# AC_Outlet_Top.net
KiCad netlist of a schematic drawn in Altium Designer
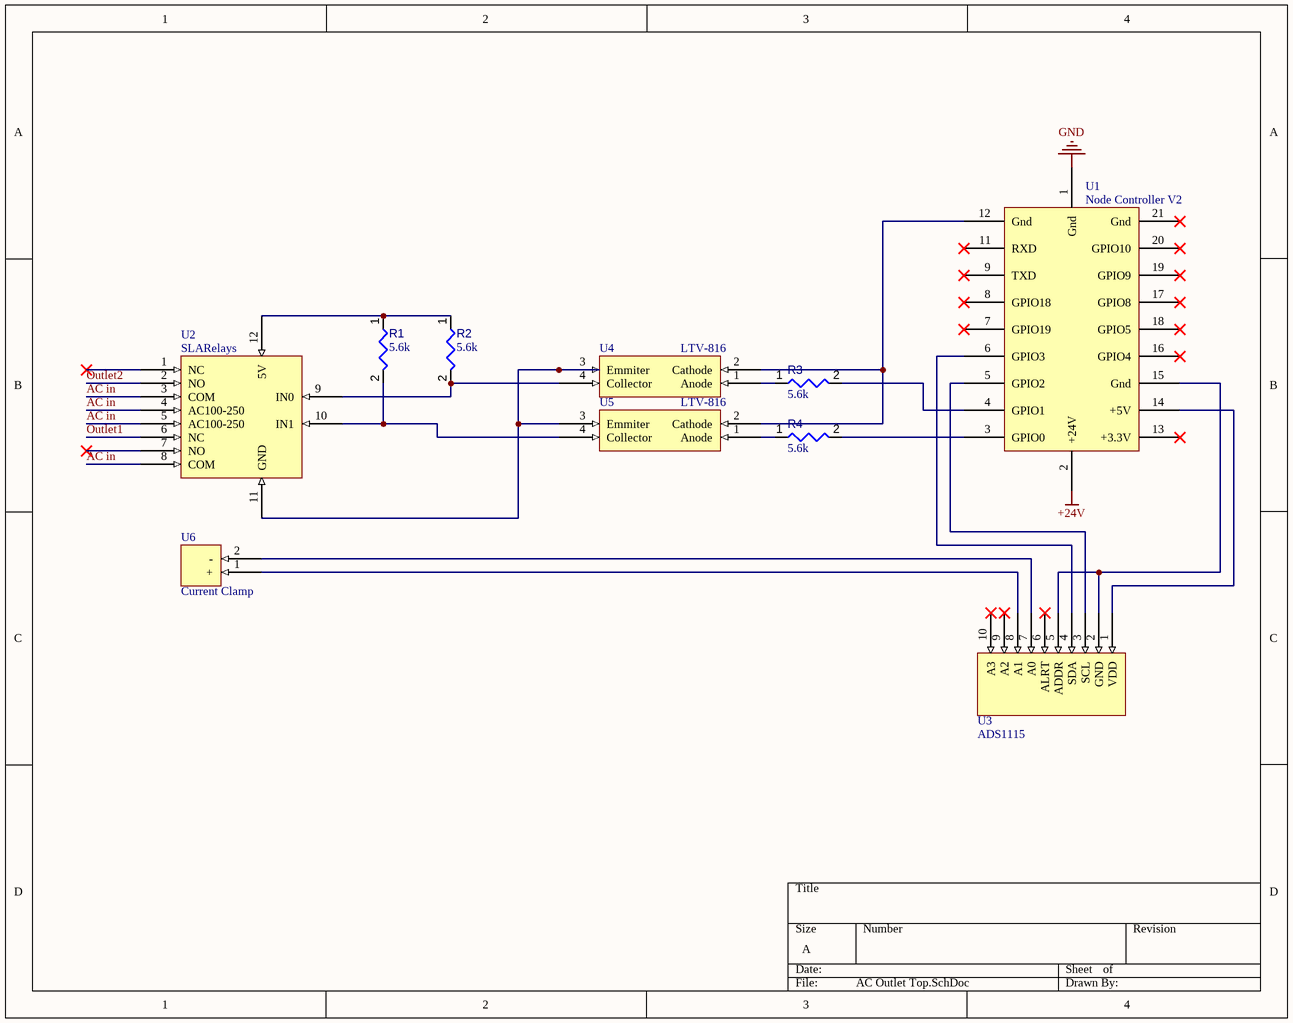
[diagram p0: AC Outlet Top.SchDoc]

(export (version "E")
  (design (tool "Eeschema 10.0.6"))
  (components
    (comp (ref "R1")
      (value "5.6k")
      (footprint "RESC0402(1005)_L")
      (description "Chip Resistor, 5,6 kOhms, +/-5 %, 63 mW, -55 to 155 degC, 0402")
      (fields (field (name "POWER") "63mW") (field (name "TOLERANCE") "5%"))
      (libsource (lib "C0514760 C0514760") (part "RES-2"))
    )
    (comp (ref "R2")
      (value "5.6k")
      (footprint "RESC0402(1005)_L")
      (description "Chip Resistor, 5,6 kOhms, +/-5 %, 63 mW, -55 to 155 degC, 0402")
      (fields (field (name "POWER") "63mW") (field (name "TOLERANCE") "5%"))
      (libsource (lib "C0514760 C0514760") (part "RES-2"))
    )
    (comp (ref "R3")
      (value "5.6k")
      (footprint "RESC0402(1005)_L")
      (description "Chip Resistor, 5,6 kOhms, +/-5 %, 63 mW, -55 to 155 degC, 0402")
      (fields (field (name "POWER") "63mW") (field (name "TOLERANCE") "5%"))
      (libsource (lib "C0514760 C0514760") (part "RES-2"))
    )
    (comp (ref "R4")
      (value "5.6k")
      (footprint "RESC0402(1005)_L")
      (description "Chip Resistor, 5,6 kOhms, +/-5 %, 63 mW, -55 to 155 degC, 0402")
      (fields (field (name "POWER") "63mW") (field (name "TOLERANCE") "5%"))
      (libsource (lib "C0514760 C0514760") (part "RES-2"))
    )
    (comp (ref "U1") (value "Node Controller V2") (libsource (lib "AC Outlet") (part "Node Controller V2")))
    (comp (ref "U2") (value "SLARelays") (libsource (lib "AC Outlet") (part "SLARelays")))
    (comp (ref "U3") (value "ADS1115") (libsource (lib "AC Outlet") (part "ADS1115")))
    (comp (ref "U4") (value "LTV-816") (libsource (lib "AC Outlet") (part "LTV-816")))
    (comp (ref "U5") (value "LTV-816") (libsource (lib "AC Outlet") (part "LTV-816")))
    (comp (ref "U6") (value "Current Clamp") (libsource (lib "AC Outlet") (part "Current Clamp")))
  )
  (nets
    (net (code "1") (name "+24V") (class "Default")
      (node (ref "U1") (pin "2") (pinfunction "+24V_2") (pintype "passive"))
    )
    (net (code "2") (name "/AC in") (class "Default")
      (node (ref "U2") (pin "3") (pinfunction "COM_3") (pintype "input"))
      (node (ref "U2") (pin "4") (pinfunction "AC100-250_4") (pintype "input"))
      (node (ref "U2") (pin "5") (pinfunction "AC100-250_5") (pintype "input"))
      (node (ref "U2") (pin "8") (pinfunction "COM_8") (pintype "input"))
    )
    (net (code "3") (name "/Outlet1") (class "Default")
      (node (ref "U2") (pin "6") (pinfunction "NC_6") (pintype "input"))
    )
    (net (code "4") (name "/Outlet2") (class "Default")
      (node (ref "U2") (pin "2") (pinfunction "NO_2") (pintype "input"))
    )
    (net (code "5") (name "GND") (class "Default")
      (node (ref "U1") (pin "1") (pinfunction "Gnd_1") (pintype "passive"))
    )
    (net (code "6") (name "Net-(U1-+5V)") (class "Default")
      (node (ref "U1") (pin "14") (pinfunction "+5V_14") (pintype "passive"))
      (node (ref "U3") (pin "1") (pinfunction "VDD_1") (pintype "input"))
    )
    (net (code "7") (name "Net-(U1-GPIO0)") (class "Default")
      (node (ref "R4") (pin "2") (pinfunction "2_2") (pintype "passive"))
      (node (ref "U1") (pin "3") (pinfunction "GPIO0_3") (pintype "passive"))
    )
    (net (code "8") (name "Net-(U1-GPIO1)") (class "Default")
      (node (ref "R3") (pin "2") (pinfunction "2_2") (pintype "passive"))
      (node (ref "U1") (pin "4") (pinfunction "GPIO1_4") (pintype "passive"))
    )
    (net (code "9") (name "Net-(U1-GPIO2)") (class "Default")
      (node (ref "U1") (pin "5") (pinfunction "GPIO2_5") (pintype "passive"))
      (node (ref "U3") (pin "3") (pinfunction "SCL_3") (pintype "input"))
    )
    (net (code "10") (name "Net-(U1-GPIO3)") (class "Default")
      (node (ref "U1") (pin "6") (pinfunction "GPIO3_6") (pintype "passive"))
      (node (ref "U3") (pin "4") (pinfunction "SDA_4") (pintype "input"))
    )
    (net (code "11") (name "Net-(U2-5V)") (class "Default")
      (node (ref "R1") (pin "1") (pinfunction "1_1") (pintype "passive"))
      (node (ref "R2") (pin "1") (pinfunction "1_1") (pintype "passive"))
      (node (ref "U2") (pin "12") (pinfunction "5V_12") (pintype "input"))
    )
    (net (code "12") (name "Net-(U2-GND)") (class "Default")
      (node (ref "U2") (pin "11") (pinfunction "GND_11") (pintype "input"))
      (node (ref "U4") (pin "3") (pinfunction "Emmiter_3") (pintype "input"))
      (node (ref "U5") (pin "3") (pinfunction "Emmiter_3") (pintype "input"))
    )
    (net (code "13") (name "Net-(U2-IN0)") (class "Default")
      (node (ref "R2") (pin "2") (pinfunction "2_2") (pintype "passive"))
      (node (ref "U2") (pin "9") (pinfunction "IN0_9") (pintype "input"))
      (node (ref "U4") (pin "4") (pinfunction "Collector_4") (pintype "input"))
    )
    (net (code "14") (name "Net-(U2-IN1)") (class "Default")
      (node (ref "R1") (pin "2") (pinfunction "2_2") (pintype "passive"))
      (node (ref "U2") (pin "10") (pinfunction "IN1_10") (pintype "input"))
      (node (ref "U5") (pin "4") (pinfunction "Collector_4") (pintype "input"))
    )
    (net (code "15") (name "Net-(U3-A0)") (class "Default")
      (node (ref "U3") (pin "7") (pinfunction "A0_7") (pintype "input"))
      (node (ref "U6") (pin "2") (pinfunction "-_2") (pintype "input"))
    )
    (net (code "16") (name "Net-(U3-A1)") (class "Default")
      (node (ref "U3") (pin "8") (pinfunction "A1_8") (pintype "input"))
      (node (ref "U6") (pin "1") (pinfunction "+_1") (pintype "input"))
    )
    (net (code "17") (name "Net-(U3-ADDR)") (class "Default")
      (node (ref "U1") (pin "15") (pinfunction "Gnd_15") (pintype "passive"))
      (node (ref "U3") (pin "2") (pinfunction "GND_2") (pintype "input"))
      (node (ref "U3") (pin "5") (pinfunction "ADDR_5") (pintype "input"))
    )
    (net (code "18") (name "Net-(U4-Anode)") (class "Default")
      (node (ref "R3") (pin "1") (pinfunction "1_1") (pintype "passive"))
      (node (ref "U4") (pin "1") (pinfunction "Anode_1") (pintype "input"))
    )
    (net (code "19") (name "Net-(U4-Cathode)") (class "Default")
      (node (ref "U1") (pin "12") (pinfunction "Gnd_12") (pintype "passive"))
      (node (ref "U4") (pin "2") (pinfunction "Cathode_2") (pintype "input"))
      (node (ref "U5") (pin "2") (pinfunction "Cathode_2") (pintype "input"))
    )
    (net (code "20") (name "Net-(U5-Anode)") (class "Default")
      (node (ref "R4") (pin "1") (pinfunction "1_1") (pintype "passive"))
      (node (ref "U5") (pin "1") (pinfunction "Anode_1") (pintype "input"))
    )
    (net (code "21") (name "unconnected-(U1-+3.3V-Pad13)") (class "Default")
      (node (ref "U1") (pin "13") (pinfunction "+3.3V_13") (pintype "passive+no_connect"))
    )
    (net (code "22") (name "unconnected-(U1-GPIO4-Pad16)") (class "Default")
      (node (ref "U1") (pin "16") (pinfunction "GPIO4_16") (pintype "passive+no_connect"))
    )
    (net (code "23") (name "unconnected-(U1-GPIO5-Pad18)") (class "Default")
      (node (ref "U1") (pin "18") (pinfunction "GPIO5_18") (pintype "passive+no_connect"))
    )
    (net (code "24") (name "unconnected-(U1-GPIO8-Pad17)") (class "Default")
      (node (ref "U1") (pin "17") (pinfunction "GPIO8_17") (pintype "passive+no_connect"))
    )
    (net (code "25") (name "unconnected-(U1-GPIO9-Pad19)") (class "Default")
      (node (ref "U1") (pin "19") (pinfunction "GPIO9_19") (pintype "passive+no_connect"))
    )
    (net (code "26") (name "unconnected-(U1-GPIO10-Pad20)") (class "Default")
      (node (ref "U1") (pin "20") (pinfunction "GPIO10_20") (pintype "passive+no_connect"))
    )
    (net (code "27") (name "unconnected-(U1-GPIO18-Pad8)") (class "Default")
      (node (ref "U1") (pin "8") (pinfunction "GPIO18_8") (pintype "passive+no_connect"))
    )
    (net (code "28") (name "unconnected-(U1-GPIO19-Pad7)") (class "Default")
      (node (ref "U1") (pin "7") (pinfunction "GPIO19_7") (pintype "passive+no_connect"))
    )
    (net (code "29") (name "unconnected-(U1-Gnd-Pad21)") (class "Default")
      (node (ref "U1") (pin "21") (pinfunction "Gnd_21") (pintype "passive+no_connect"))
    )
    (net (code "30") (name "unconnected-(U1-RXD-Pad11)") (class "Default")
      (node (ref "U1") (pin "11") (pinfunction "RXD_11") (pintype "passive+no_connect"))
    )
    (net (code "31") (name "unconnected-(U1-TXD-Pad9)") (class "Default")
      (node (ref "U1") (pin "9") (pinfunction "TXD_9") (pintype "passive+no_connect"))
    )
    (net (code "32") (name "unconnected-(U2-NC-Pad1)") (class "Default")
      (node (ref "U2") (pin "1") (pinfunction "NC_1") (pintype "input+no_connect"))
    )
    (net (code "33") (name "unconnected-(U2-NO-Pad7)") (class "Default")
      (node (ref "U2") (pin "7") (pinfunction "NO_7") (pintype "input+no_connect"))
    )
    (net (code "34") (name "unconnected-(U3-A2-Pad9)") (class "Default")
      (node (ref "U3") (pin "9") (pinfunction "A2_9") (pintype "input+no_connect"))
    )
    (net (code "35") (name "unconnected-(U3-A3-Pad10)") (class "Default")
      (node (ref "U3") (pin "10") (pinfunction "A3_10") (pintype "input+no_connect"))
    )
    (net (code "36") (name "unconnected-(U3-ALRT-Pad6)") (class "Default")
      (node (ref "U3") (pin "6") (pinfunction "ALRT_6") (pintype "input+no_connect"))
    )
  )
)
